# diff_probe.net
KiCad netlist of a schematic drawn in EAGLE
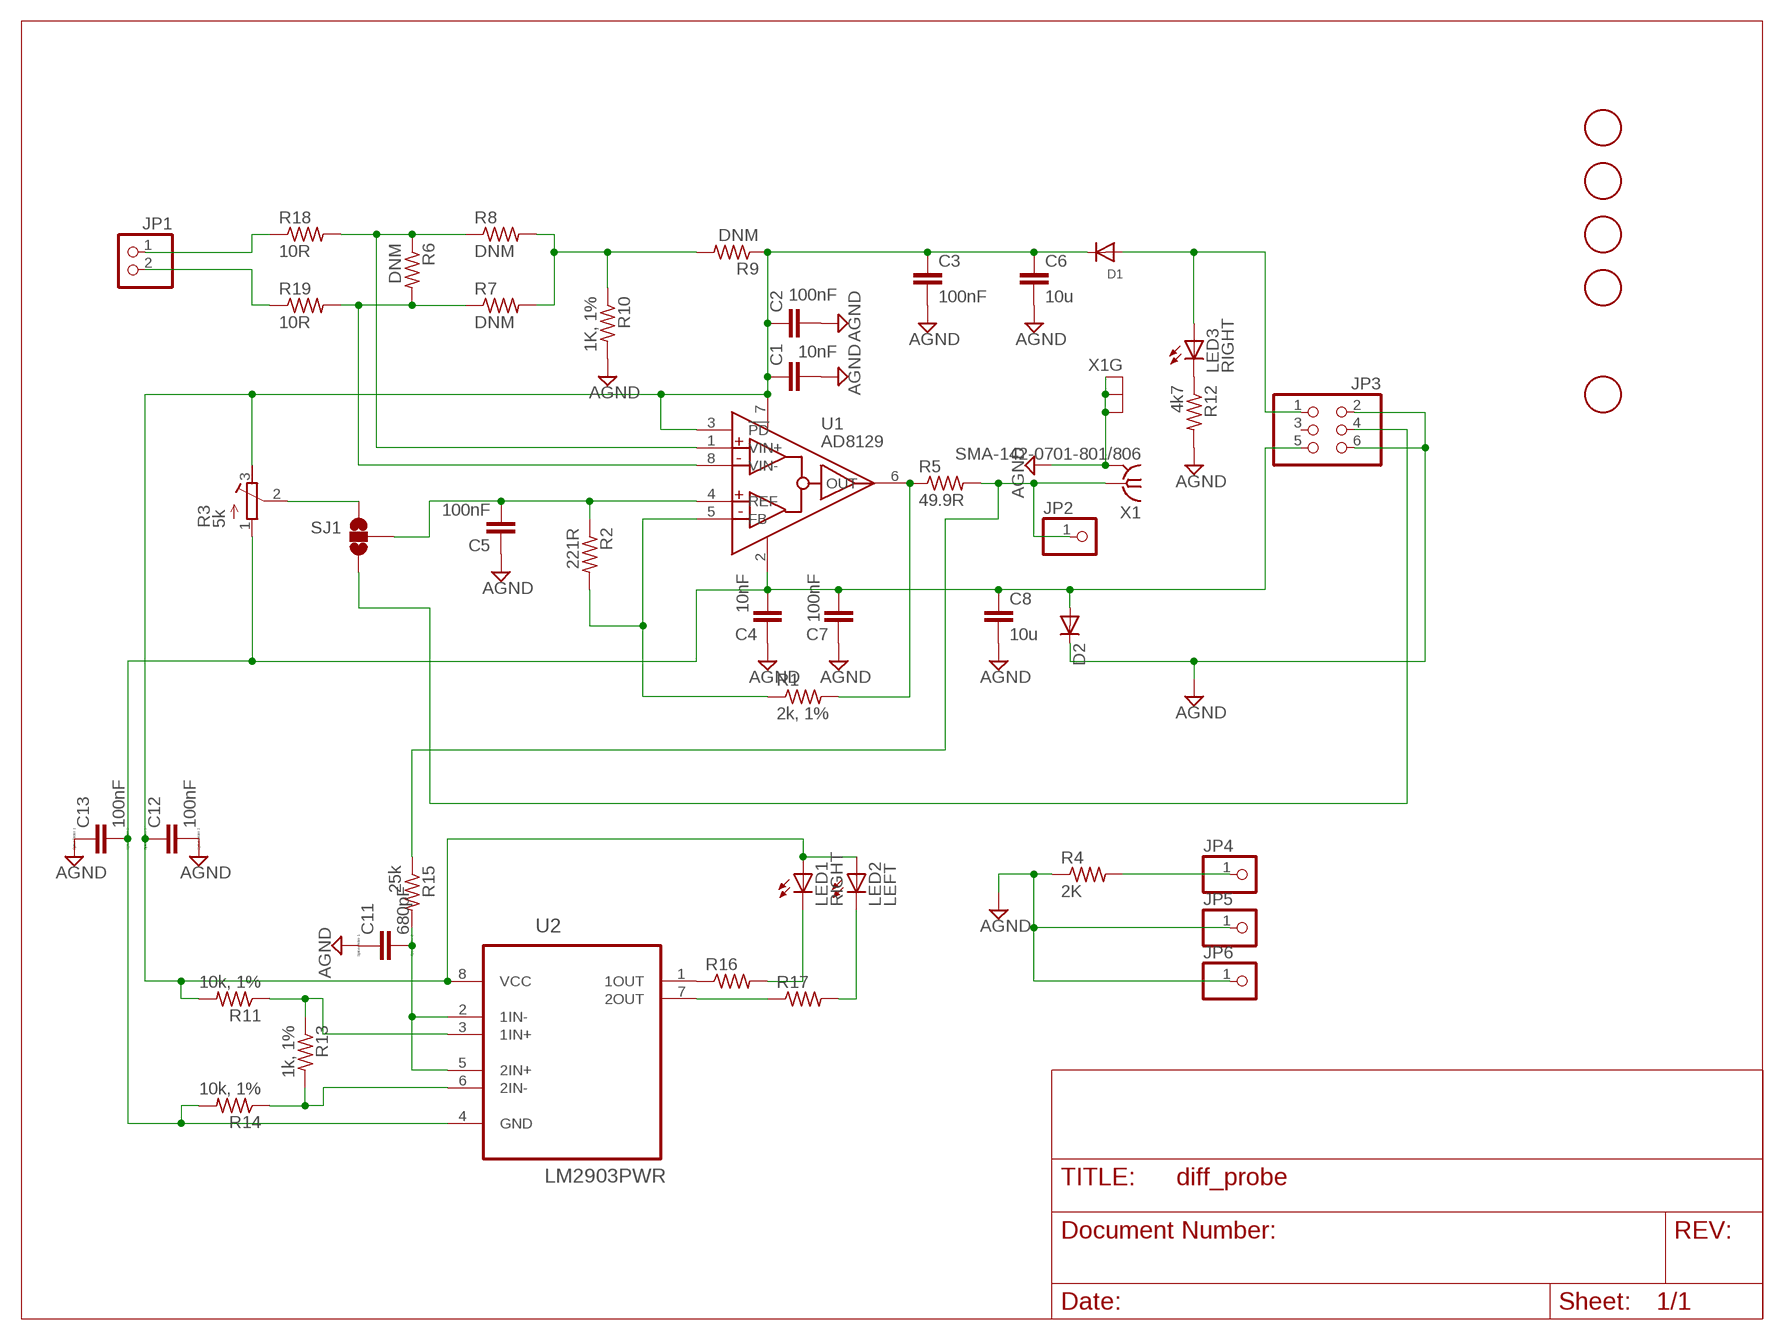
[diagram p0: schematic, sheet 1]

(export (version "E")
  (design (tool "Eeschema 10.0.6"))
  (components
    (comp (ref "C1")
      (value "10nF")
      (footprint "eagle-import:C0603")
      (libsource (lib "eagle-import") (part "C-EUC0603"))
    )
    (comp (ref "C2")
      (value "100nF")
      (footprint "eagle-import:C0603")
      (libsource (lib "eagle-import") (part "C-EUC0603"))
    )
    (comp (ref "C3")
      (value "100nF")
      (footprint "eagle-import:C0603")
      (libsource (lib "eagle-import") (part "C-EUC0603"))
    )
    (comp (ref "C4")
      (value "10nF")
      (footprint "eagle-import:C0603")
      (libsource (lib "eagle-import") (part "C-EUC0603"))
    )
    (comp (ref "C5")
      (value "100nF")
      (footprint "eagle-import:C0603")
      (libsource (lib "eagle-import") (part "C-EUC0603"))
    )
    (comp (ref "C6")
      (value "10u")
      (footprint "eagle-import:C0805")
      (libsource (lib "eagle-import") (part "C-EUC0805"))
    )
    (comp (ref "C7")
      (value "100nF")
      (footprint "eagle-import:C0603")
      (libsource (lib "eagle-import") (part "C-EUC0603"))
    )
    (comp (ref "C8")
      (value "10u")
      (footprint "eagle-import:C0805")
      (libsource (lib "eagle-import") (part "C-EUC0805"))
    )
    (comp (ref "C11")
      (value "680pF")
      (footprint "eagle-import:C0402")
      (libsource (lib "eagle-import") (part "resistor_C-EUC0402"))
    )
    (comp (ref "C12")
      (value "100nF")
      (footprint "eagle-import:C0402")
      (libsource (lib "eagle-import") (part "resistor_C-EUC0402"))
    )
    (comp (ref "C13")
      (value "100nF")
      (footprint "eagle-import:C0402")
      (libsource (lib "eagle-import") (part "resistor_C-EUC0402"))
    )
    (comp (ref "D1")
      (value "DIODESOD-123")
      (footprint "eagle-import:SOD-123")
      (libsource (lib "eagle-import") (part "DIODESOD-123"))
    )
    (comp (ref "D2")
      (value "DIODE-DO-214AC")
      (footprint "eagle-import:DO-214AC")
      (libsource (lib "eagle-import") (part "DIODE-DO-214AC"))
    )
    (comp (ref "FID1")
      (value "FIDUCIAL")
      (footprint "eagle-import:FIDUCIAL_1MM")
      (libsource (lib "eagle-import") (part "FIDUCIAL"))
    )
    (comp (ref "FID2")
      (value "FIDUCIAL")
      (footprint "eagle-import:FIDUCIAL_1MM")
      (libsource (lib "eagle-import") (part "FIDUCIAL"))
    )
    (comp (ref "FID4")
      (value "FIDUCIAL")
      (footprint "eagle-import:FIDUCIAL_1MM")
      (libsource (lib "eagle-import") (part "FIDUCIAL"))
    )
    (comp (ref "FID5")
      (value "FIDUCIAL")
      (footprint "eagle-import:FIDUCIAL_1MM")
      (libsource (lib "eagle-import") (part "FIDUCIAL"))
    )
    (comp (ref "FID6")
      (value "FIDUCIAL")
      (footprint "eagle-import:FIDUCIAL_1MM")
      (libsource (lib "eagle-import") (part "FIDUCIAL"))
    )
    (comp (ref "JP1")
      (value "PINHD-1X2/90")
      (footprint "eagle-import:1X02_90")
      (libsource (lib "eagle-import") (part "PINHD-1X2/90"))
    )
    (comp (ref "JP2")
      (value "PINHD-1X1")
      (footprint "eagle-import:1X01")
      (libsource (lib "eagle-import") (part "PINHD-1X1"))
    )
    (comp (ref "JP3")
      (value "PINHD-2X3EDGE")
      (footprint "eagle-import:6PAD_ISP")
      (libsource (lib "eagle-import") (part "PINHD-2X3EDGE"))
    )
    (comp (ref "JP4")
      (value "PINHD-1X1")
      (footprint "eagle-import:1X01")
      (libsource (lib "eagle-import") (part "PINHD-1X1"))
    )
    (comp (ref "JP5")
      (value "PINHD-1X1")
      (footprint "eagle-import:1X01")
      (libsource (lib "eagle-import") (part "PINHD-1X1"))
    )
    (comp (ref "JP6")
      (value "PINHD-1X1")
      (footprint "eagle-import:1X01")
      (libsource (lib "eagle-import") (part "PINHD-1X1"))
    )
    (comp (ref "LED1")
      (value "RIGHT")
      (footprint "eagle-import:CHIPLED_0603")
      (libsource (lib "eagle-import") (part "LEDCHIPLED_0603"))
    )
    (comp (ref "LED2")
      (value "LEFT")
      (footprint "eagle-import:CHIPLED_0603")
      (libsource (lib "eagle-import") (part "LEDCHIPLED_0603"))
    )
    (comp (ref "LED3")
      (value "RIGHT")
      (footprint "eagle-import:CHIPLED_0603")
      (libsource (lib "eagle-import") (part "LEDCHIPLED_0603"))
    )
    (comp (ref "R1")
      (value "2k, 1%")
      (footprint "eagle-import:R0603")
      (libsource (lib "eagle-import") (part "resistor_R-US_R0603"))
    )
    (comp (ref "R2")
      (value "221R")
      (footprint "eagle-import:R0603")
      (libsource (lib "eagle-import") (part "resistor_R-US_R0603"))
    )
    (comp (ref "R3")
      (value "5k")
      (footprint "eagle-import:RTRIM3224J")
      (libsource (lib "eagle-import") (part "R-TRIMM3224J"))
    )
    (comp (ref "R4")
      (value "2K")
      (footprint "eagle-import:R0603")
      (libsource (lib "eagle-import") (part "resistor_R-US_R0603"))
    )
    (comp (ref "R5")
      (value "49.9R")
      (footprint "eagle-import:R0603")
      (libsource (lib "eagle-import") (part "resistor_R-US_R0603"))
    )
    (comp (ref "R6")
      (value "DNM")
      (footprint "eagle-import:M0805")
      (libsource (lib "eagle-import") (part "resistor_R-US_M0805"))
    )
    (comp (ref "R7")
      (value "DNM")
      (footprint "eagle-import:R0603")
      (libsource (lib "eagle-import") (part "resistor_R-US_R0603"))
    )
    (comp (ref "R8")
      (value "DNM")
      (footprint "eagle-import:R0603")
      (libsource (lib "eagle-import") (part "resistor_R-US_R0603"))
    )
    (comp (ref "R9")
      (value "DNM")
      (footprint "eagle-import:R0603")
      (libsource (lib "eagle-import") (part "resistor_R-US_R0603"))
    )
    (comp (ref "R10")
      (value "1K, 1%")
      (footprint "eagle-import:R0603")
      (libsource (lib "eagle-import") (part "resistor_R-US_R0603"))
    )
    (comp (ref "R11")
      (value "10k, 1%")
      (footprint "eagle-import:R0402")
      (libsource (lib "eagle-import") (part "R-US_R0402"))
    )
    (comp (ref "R12")
      (value "4k7")
      (footprint "eagle-import:R0603")
      (libsource (lib "eagle-import") (part "resistor_R-US_R0603"))
    )
    (comp (ref "R13")
      (value "1k, 1%")
      (footprint "eagle-import:R0402")
      (libsource (lib "eagle-import") (part "R-US_R0402"))
    )
    (comp (ref "R14")
      (value "10k, 1%")
      (footprint "eagle-import:R0402")
      (libsource (lib "eagle-import") (part "R-US_R0402"))
    )
    (comp (ref "R15")
      (value "25k")
      (footprint "eagle-import:R0402")
      (libsource (lib "eagle-import") (part "R-US_R0402"))
    )
    (comp (ref "R16")
      (value "R-US_R0402")
      (footprint "eagle-import:R0402")
      (libsource (lib "eagle-import") (part "R-US_R0402"))
    )
    (comp (ref "R17")
      (value "R-US_R0402")
      (footprint "eagle-import:R0402")
      (libsource (lib "eagle-import") (part "R-US_R0402"))
    )
    (comp (ref "R18")
      (value "10R")
      (footprint "eagle-import:R0603")
      (libsource (lib "eagle-import") (part "resistor_R-US_R0603"))
    )
    (comp (ref "R19")
      (value "10R")
      (footprint "eagle-import:R0603")
      (libsource (lib "eagle-import") (part "resistor_R-US_R0603"))
    )
    (comp (ref "SJ1")
      (value "SOLDERJUMPER_2WAYPASTE1&2")
      (footprint "eagle-import:SJ_3_PASTE1&2")
      (libsource (lib "eagle-import") (part "SOLDERJUMPER_2WAYPASTE1&2"))
    )
    (comp (ref "U1")
      (value "AD8129")
      (footprint "eagle-import:SO08")
      (libsource (lib "eagle-import") (part "AD8129"))
    )
    (comp (ref "U2")
      (value "LM2903PWR")
      (footprint "eagle-import:SOP65P640X120-8N")
      (libsource (lib "eagle-import") (part "LM2903PWR"))
    )
    (comp (ref "X1")
      (value "SMA-142-0701-801/806")
      (footprint "eagle-import:J502-ND-142-0701-801_806")
      (fields (field (name "MF") "JOHNSON COMPONENTS") (field (name "MPN") "142-0701-801"))
      (libsource (lib "eagle-import") (part "SMA-142-0701-801/806"))
    )
  )
  (nets
    (net (code "1") (name "AGND") (class "Default")
      (node (ref "C1") (pin "2") (pinfunction "2_2") (pintype "passive"))
      (node (ref "C11") (pin "1") (pinfunction "1_1") (pintype "passive"))
      (node (ref "C12") (pin "2") (pinfunction "2_2") (pintype "passive"))
      (node (ref "C13") (pin "1") (pinfunction "1_1") (pintype "passive"))
      (node (ref "C2") (pin "2") (pinfunction "2_2") (pintype "passive"))
      (node (ref "C3") (pin "2") (pinfunction "2_2") (pintype "passive"))
      (node (ref "C4") (pin "1") (pinfunction "1_1") (pintype "passive"))
      (node (ref "C5") (pin "1") (pinfunction "1_1") (pintype "passive"))
      (node (ref "C6") (pin "2") (pinfunction "2_2") (pintype "passive"))
      (node (ref "C7") (pin "1") (pinfunction "1_1") (pintype "passive"))
      (node (ref "C8") (pin "2") (pinfunction "2_2") (pintype "passive"))
      (node (ref "D2") (pin "C") (pinfunction "C_C") (pintype "passive"))
      (node (ref "JP3") (pin "2") (pinfunction "1_2") (pintype "passive"))
      (node (ref "JP3") (pin "6") (pinfunction "5_6") (pintype "passive"))
      (node (ref "JP5") (pin "1") (pinfunction "1_1") (pintype "passive"))
      (node (ref "JP6") (pin "1") (pinfunction "1_1") (pintype "passive"))
      (node (ref "R10") (pin "2") (pinfunction "2_2") (pintype "passive"))
      (node (ref "R12") (pin "2") (pinfunction "2_2") (pintype "passive"))
      (node (ref "R4") (pin "1") (pinfunction "1_1") (pintype "passive"))
      (node (ref "X1") (pin "G@1") (pinfunction "GND_G@1") (pintype "power_in"))
      (node (ref "X1") (pin "G@2") (pinfunction "GND_G@2") (pintype "power_in"))
      (node (ref "X1") (pin "G@3") (pinfunction "GND_G@3") (pintype "power_in"))
      (node (ref "X1") (pin "G@4") (pinfunction "GND_G@4") (pintype "power_in"))
    )
    (net (code "2") (name "Net-(JP1-Pad1)") (class "Default")
      (node (ref "JP1") (pin "1") (pinfunction "1_1") (pintype "passive"))
      (node (ref "R18") (pin "1") (pinfunction "1_1") (pintype "passive"))
    )
    (net (code "3") (name "Net-(JP1-Pad2)") (class "Default")
      (node (ref "JP1") (pin "2") (pinfunction "2_2") (pintype "passive"))
      (node (ref "R19") (pin "1") (pinfunction "1_1") (pintype "passive"))
    )
    (net (code "4") (name "Net-(JP2-Pad1)") (class "Default")
      (node (ref "JP2") (pin "1") (pinfunction "1_1") (pintype "passive"))
      (node (ref "R15") (pin "1") (pinfunction "1_1") (pintype "passive"))
      (node (ref "R5") (pin "2") (pinfunction "2_2") (pintype "passive"))
      (node (ref "X1") (pin "1") (pinfunction "1_1") (pintype "passive"))
    )
    (net (code "5") (name "Net-(JP3-2)") (class "Default")
      (node (ref "D1") (pin "A") (pinfunction "A_A") (pintype "passive"))
      (node (ref "JP3") (pin "1") (pinfunction "2_1") (pintype "passive"))
      (node (ref "LED3") (pin "A") (pinfunction "A_A") (pintype "passive"))
    )
    (net (code "6") (name "Net-(JP3-3)") (class "Default")
      (node (ref "JP3") (pin "4") (pinfunction "3_4") (pintype "passive"))
      (node (ref "SJ1") (pin "3") (pinfunction "3_3") (pintype "passive"))
    )
    (net (code "7") (name "Net-(JP3-6)") (class "Default")
      (node (ref "C13") (pin "2") (pinfunction "2_2") (pintype "passive"))
      (node (ref "C4") (pin "2") (pinfunction "2_2") (pintype "passive"))
      (node (ref "C7") (pin "2") (pinfunction "2_2") (pintype "passive"))
      (node (ref "C8") (pin "1") (pinfunction "1_1") (pintype "passive"))
      (node (ref "D2") (pin "A") (pinfunction "A_A") (pintype "passive"))
      (node (ref "JP3") (pin "5") (pinfunction "6_5") (pintype "passive"))
      (node (ref "R14") (pin "2") (pinfunction "2_2") (pintype "passive"))
      (node (ref "R3") (pin "1") (pinfunction "E_1") (pintype "passive"))
      (node (ref "U1") (pin "2") (pinfunction "VSS_2") (pintype "power_in"))
      (node (ref "U2") (pin "4") (pinfunction "GND_4") (pintype "passive"))
    )
    (net (code "8") (name "Net-(JP4-Pad1)") (class "Default")
      (node (ref "JP4") (pin "1") (pinfunction "1_1") (pintype "passive"))
      (node (ref "R4") (pin "2") (pinfunction "2_2") (pintype "passive"))
    )
    (net (code "9") (name "Net-(LED1-PadC)") (class "Default")
      (node (ref "LED1") (pin "C") (pinfunction "C_C") (pintype "passive"))
      (node (ref "R16") (pin "2") (pinfunction "2_2") (pintype "passive"))
    )
    (net (code "10") (name "Net-(LED2-PadC)") (class "Default")
      (node (ref "LED2") (pin "C") (pinfunction "C_C") (pintype "passive"))
      (node (ref "R17") (pin "2") (pinfunction "2_2") (pintype "passive"))
    )
    (net (code "11") (name "Net-(LED3-PadC)") (class "Default")
      (node (ref "LED3") (pin "C") (pinfunction "C_C") (pintype "passive"))
      (node (ref "R12") (pin "1") (pinfunction "1_1") (pintype "passive"))
    )
    (net (code "12") (name "Net-(R3-A)") (class "Default")
      (node (ref "C1") (pin "1") (pinfunction "1_1") (pintype "passive"))
      (node (ref "C12") (pin "1") (pinfunction "1_1") (pintype "passive"))
      (node (ref "C2") (pin "1") (pinfunction "1_1") (pintype "passive"))
      (node (ref "C3") (pin "1") (pinfunction "1_1") (pintype "passive"))
      (node (ref "C6") (pin "1") (pinfunction "1_1") (pintype "passive"))
      (node (ref "D1") (pin "C") (pinfunction "C_C") (pintype "passive"))
      (node (ref "LED1") (pin "A") (pinfunction "A_A") (pintype "passive"))
      (node (ref "LED2") (pin "A") (pinfunction "A_A") (pintype "passive"))
      (node (ref "R11") (pin "2") (pinfunction "2_2") (pintype "passive"))
      (node (ref "R3") (pin "3") (pinfunction "A_3") (pintype "passive"))
      (node (ref "R9") (pin "1") (pinfunction "1_1") (pintype "passive"))
      (node (ref "U1") (pin "3") (pinfunction "~{PD}_3") (pintype "bidirectional"))
      (node (ref "U1") (pin "7") (pinfunction "VCC_7") (pintype "power_in"))
      (node (ref "U2") (pin "8") (pinfunction "VCC_8") (pintype "power_in"))
    )
    (net (code "13") (name "Net-(R3-S)") (class "Default")
      (node (ref "R3") (pin "2") (pinfunction "S_2") (pintype "passive"))
      (node (ref "SJ1") (pin "1") (pinfunction "1_1") (pintype "passive"))
    )
    (net (code "14") (name "Net-(R10-Pad1)") (class "Default")
      (node (ref "R10") (pin "1") (pinfunction "1_1") (pintype "passive"))
      (node (ref "R7") (pin "2") (pinfunction "2_2") (pintype "passive"))
      (node (ref "R8") (pin "2") (pinfunction "2_2") (pintype "passive"))
      (node (ref "R9") (pin "2") (pinfunction "2_2") (pintype "passive"))
    )
    (net (code "15") (name "Net-(U1-FB)") (class "Default")
      (node (ref "R1") (pin "1") (pinfunction "1_1") (pintype "passive"))
      (node (ref "R2") (pin "2") (pinfunction "2_2") (pintype "passive"))
      (node (ref "U1") (pin "5") (pinfunction "FB_5") (pintype "bidirectional"))
    )
    (net (code "16") (name "Net-(U1-OUT)") (class "Default")
      (node (ref "R1") (pin "2") (pinfunction "2_2") (pintype "passive"))
      (node (ref "R5") (pin "1") (pinfunction "1_1") (pintype "passive"))
      (node (ref "U1") (pin "6") (pinfunction "OUT_6") (pintype "bidirectional"))
    )
    (net (code "17") (name "Net-(U1-REF)") (class "Default")
      (node (ref "C5") (pin "2") (pinfunction "2_2") (pintype "passive"))
      (node (ref "R2") (pin "1") (pinfunction "1_1") (pintype "passive"))
      (node (ref "SJ1") (pin "2") (pinfunction "2_2") (pintype "passive"))
      (node (ref "U1") (pin "4") (pinfunction "REF_4") (pintype "bidirectional"))
    )
    (net (code "18") (name "Net-(U1-VIN+)") (class "Default")
      (node (ref "R18") (pin "2") (pinfunction "2_2") (pintype "passive"))
      (node (ref "R6") (pin "1") (pinfunction "1_1") (pintype "passive"))
      (node (ref "R8") (pin "1") (pinfunction "1_1") (pintype "passive"))
      (node (ref "U1") (pin "1") (pinfunction "VIN+_1") (pintype "bidirectional"))
    )
    (net (code "19") (name "Net-(U1-VIN-)") (class "Default")
      (node (ref "R19") (pin "2") (pinfunction "2_2") (pintype "passive"))
      (node (ref "R6") (pin "2") (pinfunction "2_2") (pintype "passive"))
      (node (ref "R7") (pin "1") (pinfunction "1_1") (pintype "passive"))
      (node (ref "U1") (pin "8") (pinfunction "VIN-_8") (pintype "bidirectional"))
    )
    (net (code "20") (name "Net-(U2-1IN+)") (class "Default")
      (node (ref "R11") (pin "1") (pinfunction "1_1") (pintype "passive"))
      (node (ref "R13") (pin "1") (pinfunction "1_1") (pintype "passive"))
      (node (ref "U2") (pin "3") (pinfunction "1IN+_3") (pintype "input"))
    )
    (net (code "21") (name "Net-(U2-1IN-)") (class "Default")
      (node (ref "C11") (pin "2") (pinfunction "2_2") (pintype "passive"))
      (node (ref "R15") (pin "2") (pinfunction "2_2") (pintype "passive"))
      (node (ref "U2") (pin "2") (pinfunction "1IN-_2") (pintype "input"))
      (node (ref "U2") (pin "5") (pinfunction "2IN+_5") (pintype "input"))
    )
    (net (code "22") (name "Net-(U2-1OUT)") (class "Default")
      (node (ref "R16") (pin "1") (pinfunction "1_1") (pintype "passive"))
      (node (ref "U2") (pin "1") (pinfunction "1OUT_1") (pintype "output"))
    )
    (net (code "23") (name "Net-(U2-2IN-)") (class "Default")
      (node (ref "R13") (pin "2") (pinfunction "2_2") (pintype "passive"))
      (node (ref "R14") (pin "1") (pinfunction "1_1") (pintype "passive"))
      (node (ref "U2") (pin "6") (pinfunction "2IN-_6") (pintype "input"))
    )
    (net (code "24") (name "Net-(U2-2OUT)") (class "Default")
      (node (ref "R17") (pin "1") (pinfunction "1_1") (pintype "passive"))
      (node (ref "U2") (pin "7") (pinfunction "2OUT_7") (pintype "output"))
    )
    (net (code "25") (name "unconnected-(JP3-4-Pad3)") (class "Default")
      (node (ref "JP3") (pin "3") (pinfunction "4_3") (pintype "passive"))
    )
  )
)
